# BpodFSM_r2_2.net
KiCad netlist of a schematic drawn in EAGLE
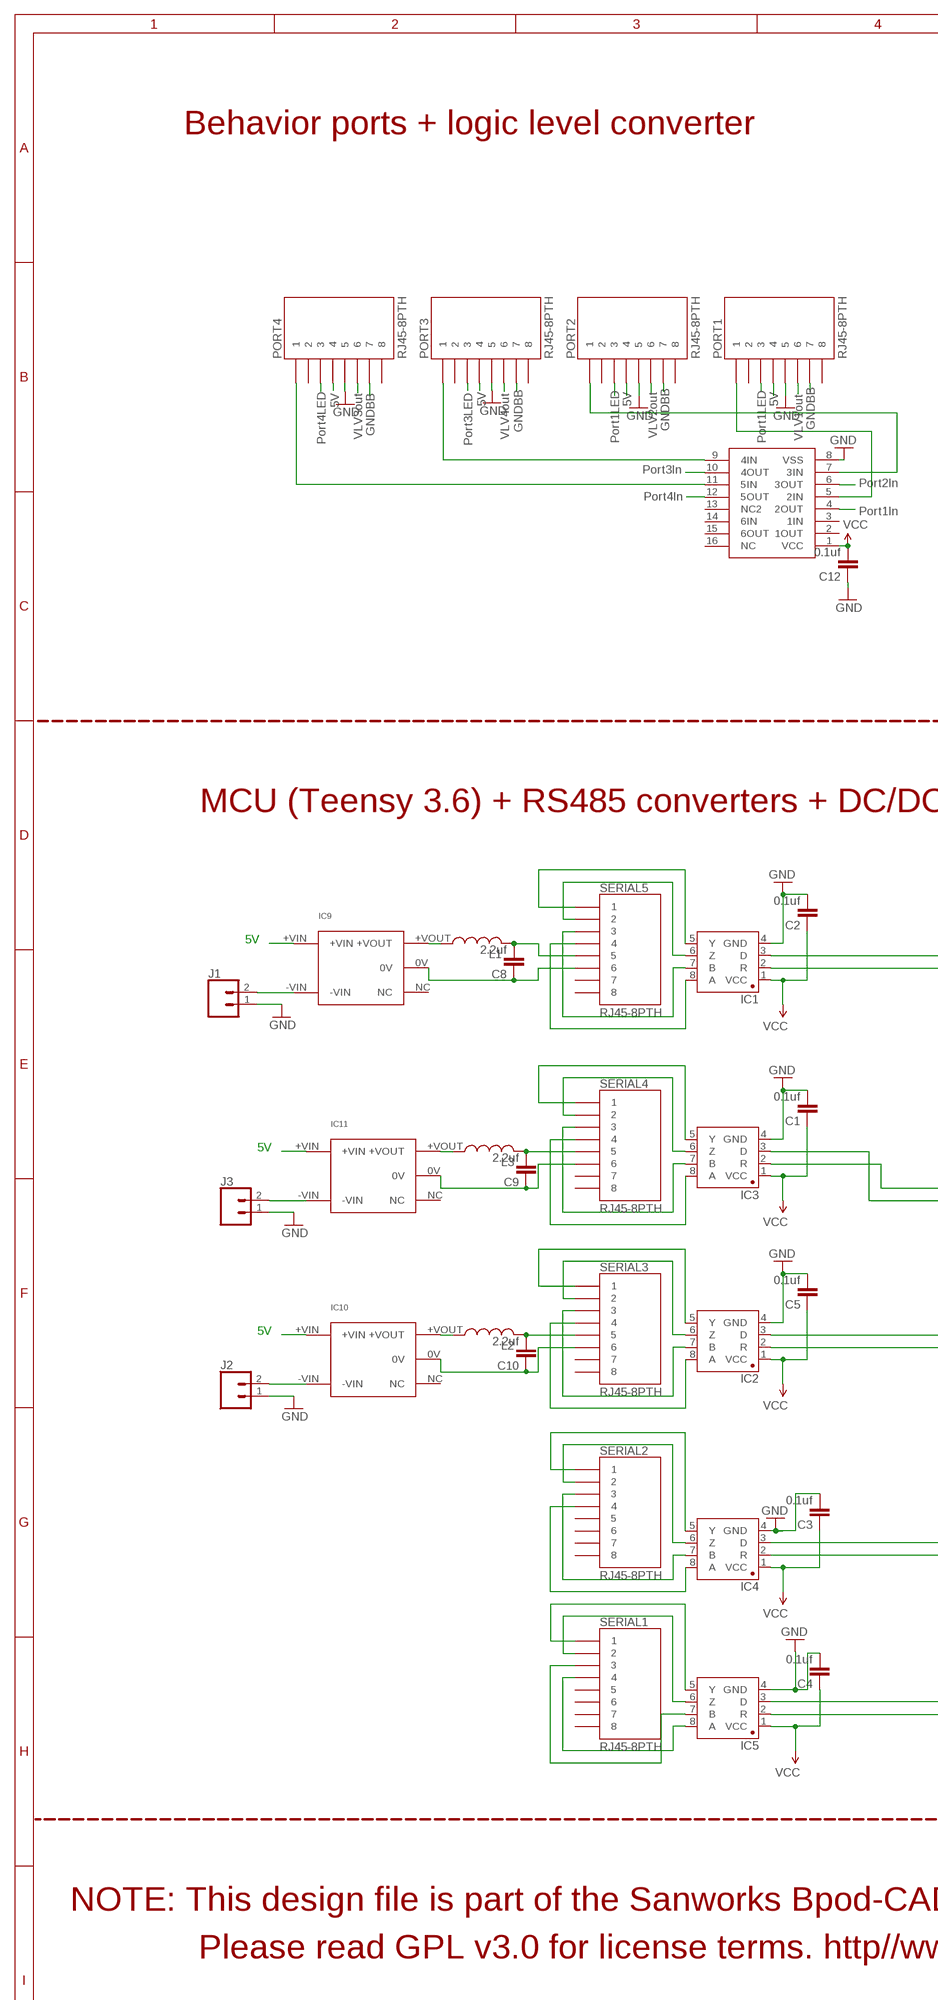
[diagram p0: schematic, sheet 1, part 1 of 2]
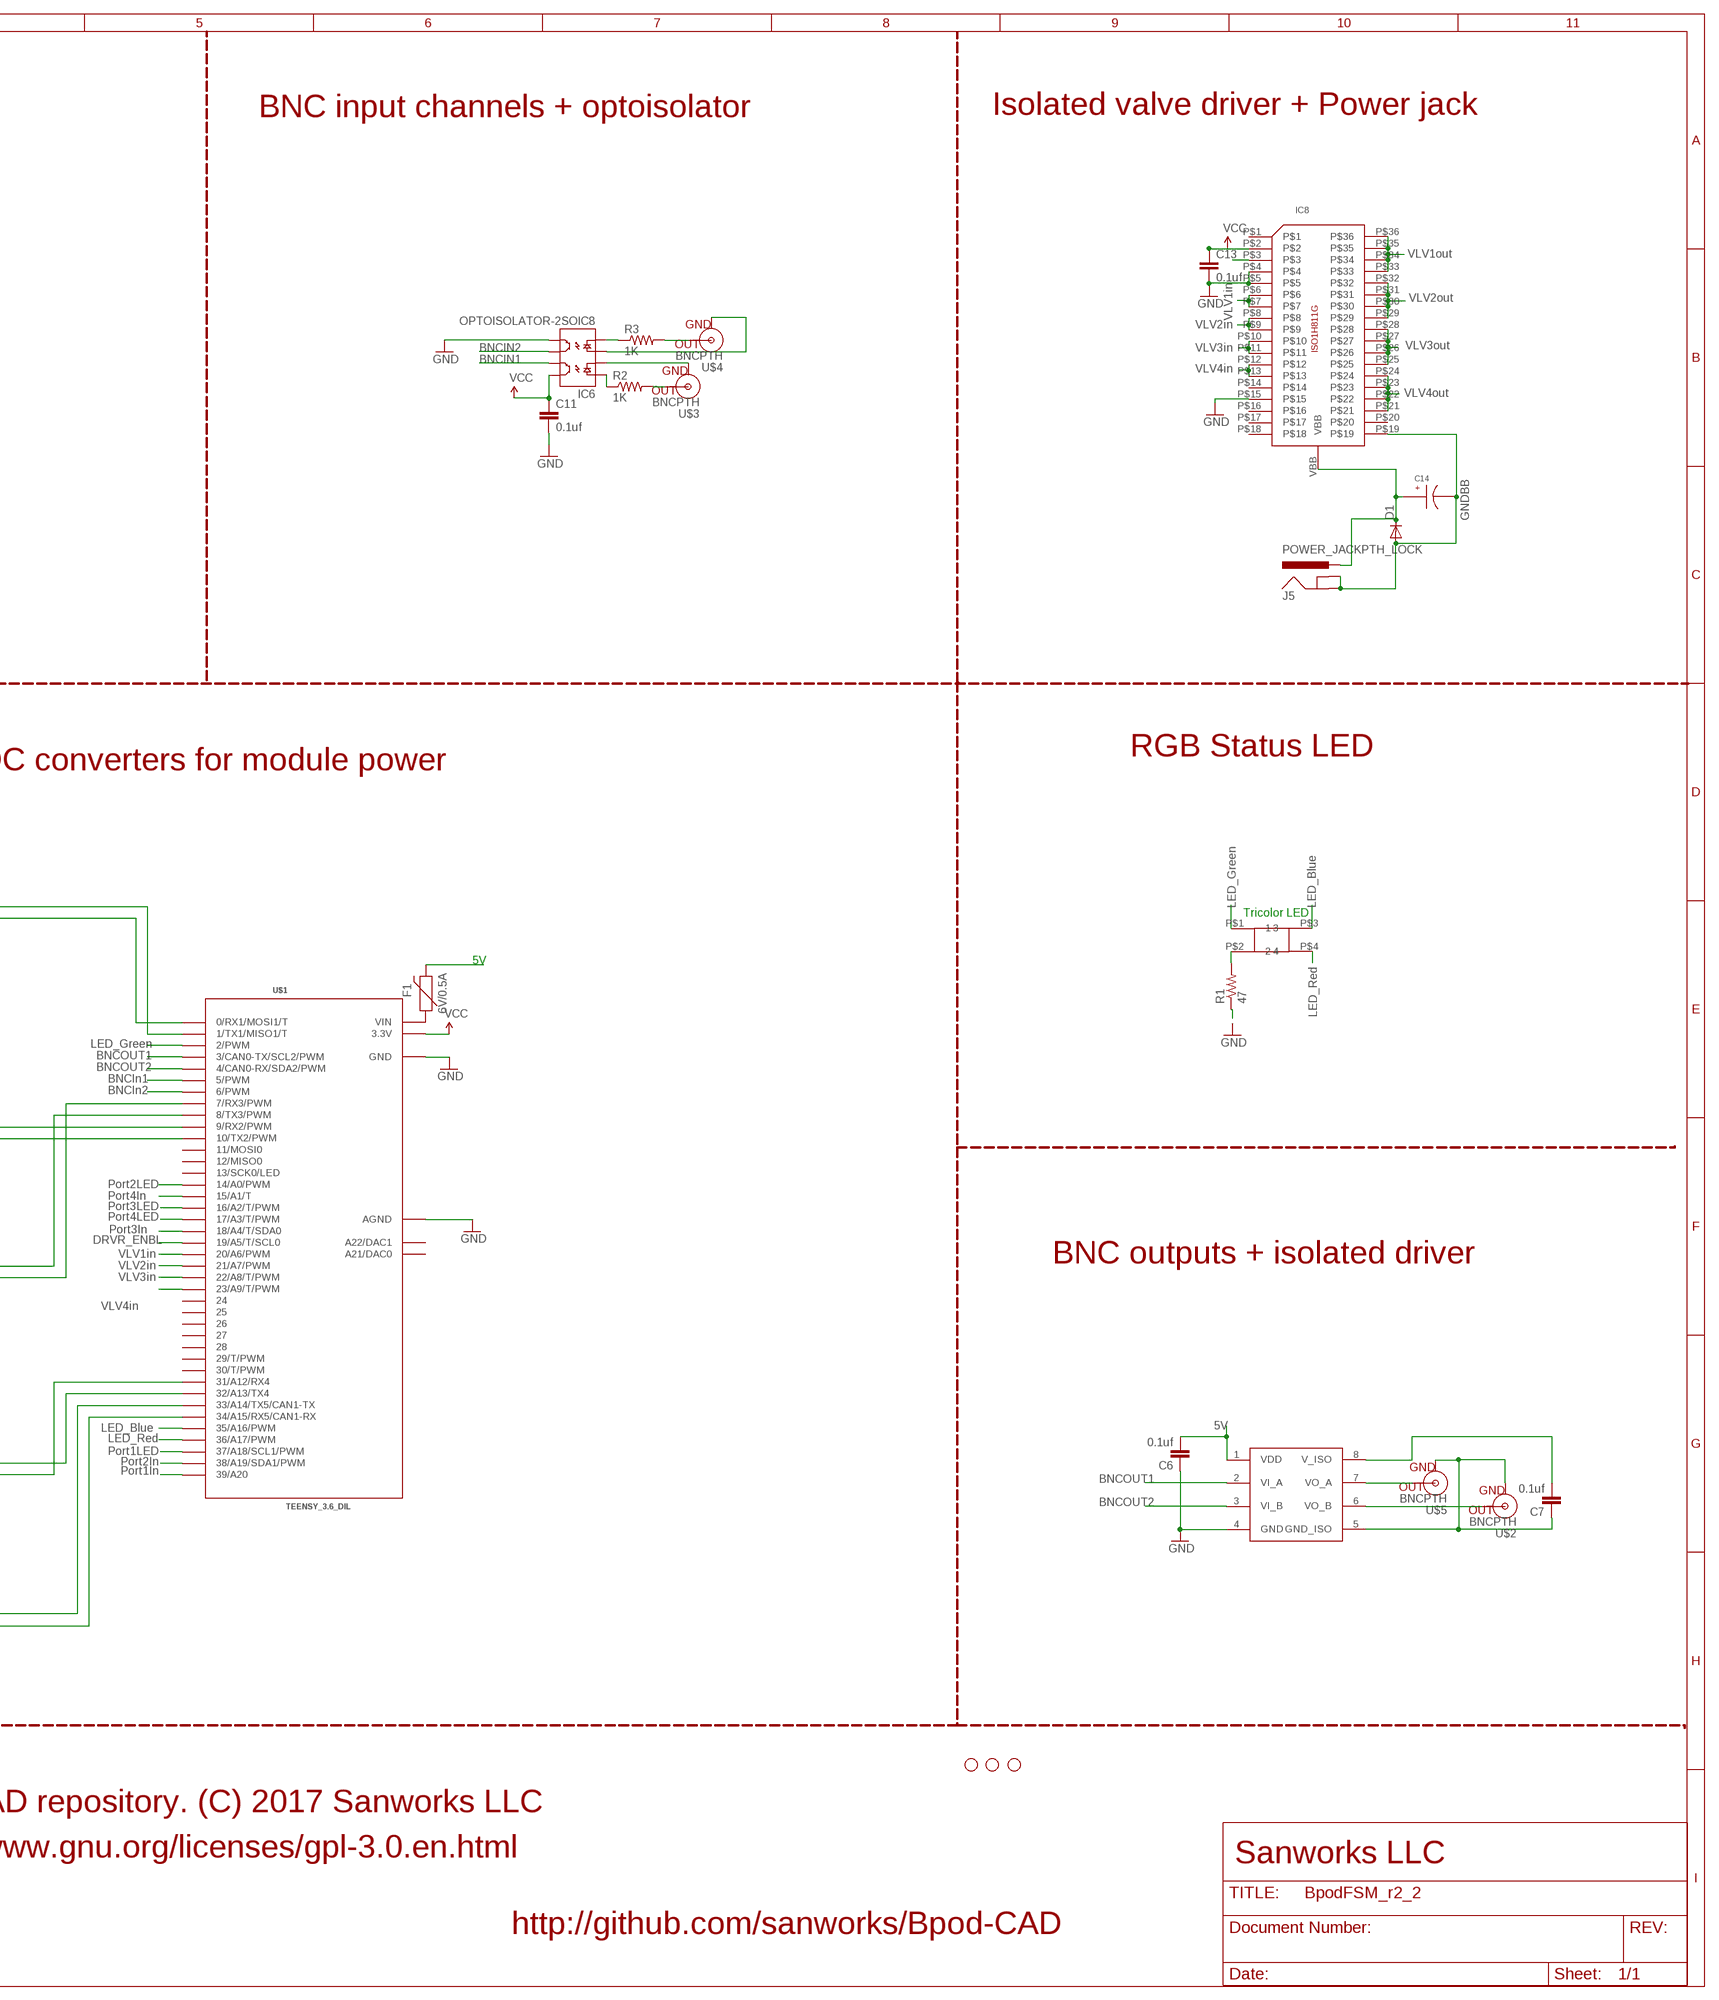
[diagram p1: schematic, sheet 1, part 2 of 2]

(export (version "E")
  (design (tool "Eeschema 10.0.6"))
  (components
    (comp (ref "C1")
      (value "0.1uf")
      (footprint "eagle-import:1206")
      (libsource (lib "eagle-import") (part "CAP1206"))
    )
    (comp (ref "C2")
      (value "0.1uf")
      (footprint "eagle-import:1206")
      (libsource (lib "eagle-import") (part "CAP1206"))
    )
    (comp (ref "C3")
      (value "0.1uf")
      (footprint "eagle-import:1206")
      (libsource (lib "eagle-import") (part "CAP1206"))
    )
    (comp (ref "C4")
      (value "0.1uf")
      (footprint "eagle-import:1206")
      (libsource (lib "eagle-import") (part "CAP1206"))
    )
    (comp (ref "C5")
      (value "0.1uf")
      (footprint "eagle-import:1206")
      (libsource (lib "eagle-import") (part "CAP1206"))
    )
    (comp (ref "C6")
      (value "0.1uf")
      (footprint "eagle-import:1206")
      (libsource (lib "eagle-import") (part "CAP1206"))
    )
    (comp (ref "C7")
      (value "0.1uf")
      (footprint "eagle-import:1206")
      (libsource (lib "eagle-import") (part "CAP1206"))
    )
    (comp (ref "C8")
      (value "2.2uf")
      (footprint "eagle-import:1206")
      (libsource (lib "eagle-import") (part "CAP1206"))
    )
    (comp (ref "C9")
      (value "2.2uf")
      (footprint "eagle-import:1206")
      (libsource (lib "eagle-import") (part "CAP1206"))
    )
    (comp (ref "C10")
      (value "2.2uf")
      (footprint "eagle-import:1206")
      (libsource (lib "eagle-import") (part "CAP1206"))
    )
    (comp (ref "C11")
      (value "0.1uf")
      (footprint "eagle-import:1206")
      (libsource (lib "eagle-import") (part "CAP1206"))
    )
    (comp (ref "C12")
      (value "0.1uf")
      (footprint "eagle-import:1206")
      (libsource (lib "eagle-import") (part "CAP1206"))
    )
    (comp (ref "C13")
      (value "0.1uf")
      (footprint "eagle-import:1206")
      (libsource (lib "eagle-import") (part "CAP1206"))
    )
    (comp (ref "C14")
      (value "EEE-FK1H100UR")
      (footprint "eagle-import:EEE-FK1H100UR")
      (libsource (lib "eagle-import") (part "EEE-FK1H100UR"))
    )
    (comp (ref "D1")
      (value "DIODE-DO214AA")
      (footprint "eagle-import:DO214AA")
      (libsource (lib "eagle-import") (part "DIODE-DO214AA"))
    )
    (comp (ref "F1")
      (value "6V/0.5A")
      (footprint "eagle-import:1206")
      (libsource (lib "eagle-import") (part "PPTC_HALF-AMP"))
    )
    (comp (ref "IC1")
      (value "SN65HVD31DR")
      (footprint "eagle-import:SO08")
      (libsource (lib "eagle-import") (part "SN65HVD31DR"))
    )
    (comp (ref "IC2")
      (value "SN65HVD31DR")
      (footprint "eagle-import:SO08")
      (libsource (lib "eagle-import") (part "SN65HVD31DR"))
    )
    (comp (ref "IC3")
      (value "SN65HVD31DR")
      (footprint "eagle-import:SO08")
      (libsource (lib "eagle-import") (part "SN65HVD31DR"))
    )
    (comp (ref "IC4")
      (value "SN65HVD31DR")
      (footprint "eagle-import:SO08")
      (libsource (lib "eagle-import") (part "SN65HVD31DR"))
    )
    (comp (ref "IC5")
      (value "SN65HVD31DR")
      (footprint "eagle-import:SO08")
      (libsource (lib "eagle-import") (part "SN65HVD31DR"))
    )
    (comp (ref "IC6")
      (value "OPTOISOLATOR-2SOIC8")
      (footprint "eagle-import:SO08-2")
      (libsource (lib "eagle-import") (part "OPTOISOLATOR-2SOIC8"))
    )
    (comp (ref "IC7")
      (value "ADUM5240")
      (footprint "eagle-import:SO08")
      (libsource (lib "eagle-import") (part "ADUM5240"))
    )
    (comp (ref "IC8")
      (value "ISO1H811G")
      (footprint "eagle-import:ISO1H811G")
      (libsource (lib "eagle-import") (part "ISO1H811G"))
    )
    (comp (ref "IC9")
      (value "MTU1D0505MC")
      (footprint "eagle-import:MTU1D0505MC")
      (libsource (lib "eagle-import") (part "MTU1D0505MC"))
    )
    (comp (ref "IC10")
      (value "MTU1D0505MC")
      (footprint "eagle-import:MTU1D0505MC")
      (libsource (lib "eagle-import") (part "MTU1D0505MC"))
    )
    (comp (ref "IC11")
      (value "MTU1D0505MC")
      (footprint "eagle-import:MTU1D0505MC")
      (libsource (lib "eagle-import") (part "MTU1D0505MC"))
    )
    (comp (ref "IC12")
      (value "CD4050")
      (footprint "eagle-import:SO16")
      (libsource (lib "eagle-import") (part "CD4050"))
    )
    (comp (ref "J1")
      (value "CONN_02")
      (footprint "eagle-import:1X02")
      (libsource (lib "eagle-import") (part "CONN_02"))
    )
    (comp (ref "J2")
      (value "CONN_02")
      (footprint "eagle-import:1X02")
      (libsource (lib "eagle-import") (part "CONN_02"))
    )
    (comp (ref "J3")
      (value "CONN_02")
      (footprint "eagle-import:1X02")
      (libsource (lib "eagle-import") (part "CONN_02"))
    )
    (comp (ref "J5")
      (value "POWER_JACKPTH_LOCK")
      (footprint "eagle-import:POWER_JACK_PTH_LOCK")
      (libsource (lib "eagle-import") (part "POWER_JACKPTH_LOCK"))
    )
    (comp (ref "JP3")
      (value "STAND-OFF")
      (footprint "eagle-import:STAND-OFF")
      (libsource (lib "eagle-import") (part "STAND-OFF"))
    )
    (comp (ref "JP4")
      (value "STAND-OFF")
      (footprint "eagle-import:STAND-OFF")
      (libsource (lib "eagle-import") (part "STAND-OFF"))
    )
    (comp (ref "JP5")
      (value "STAND-OFF")
      (footprint "eagle-import:STAND-OFF")
      (libsource (lib "eagle-import") (part "STAND-OFF"))
    )
    (comp (ref "L1")
      (value "L-USL3225M")
      (footprint "eagle-import:L3225M")
      (libsource (lib "eagle-import") (part "L-USL3225M"))
    )
    (comp (ref "L2")
      (value "L-USL3225M")
      (footprint "eagle-import:L3225M")
      (libsource (lib "eagle-import") (part "L-USL3225M"))
    )
    (comp (ref "L3")
      (value "L-USL3225M")
      (footprint "eagle-import:L3225M")
      (libsource (lib "eagle-import") (part "L-USL3225M"))
    )
    (comp (ref "PORT1")
      (value "RJ45-8PTH")
      (footprint "eagle-import:RJ45-8")
      (libsource (lib "eagle-import") (part "RJ45-8PTH"))
    )
    (comp (ref "PORT2")
      (value "RJ45-8PTH")
      (footprint "eagle-import:RJ45-8")
      (libsource (lib "eagle-import") (part "RJ45-8PTH"))
    )
    (comp (ref "PORT3")
      (value "RJ45-8PTH")
      (footprint "eagle-import:RJ45-8")
      (libsource (lib "eagle-import") (part "RJ45-8PTH"))
    )
    (comp (ref "PORT4")
      (value "RJ45-8PTH")
      (footprint "eagle-import:RJ45-8")
      (libsource (lib "eagle-import") (part "RJ45-8PTH"))
    )
    (comp (ref "R1")
      (value "47")
      (footprint "eagle-import:1206")
      (libsource (lib "eagle-import") (part "RESISTOR1206"))
    )
    (comp (ref "R2")
      (value "1K")
      (footprint "eagle-import:1206")
      (libsource (lib "eagle-import") (part "SparkFun-Resistors_RESISTOR1206"))
    )
    (comp (ref "R3")
      (value "1K")
      (footprint "eagle-import:1206")
      (libsource (lib "eagle-import") (part "SparkFun-Resistors_RESISTOR1206"))
    )
    (comp (ref "SERIAL1")
      (value "RJ45-8PTH")
      (footprint "eagle-import:RJ45-8")
      (libsource (lib "eagle-import") (part "RJ45-8PTH"))
    )
    (comp (ref "SERIAL2")
      (value "RJ45-8PTH")
      (footprint "eagle-import:RJ45-8")
      (libsource (lib "eagle-import") (part "RJ45-8PTH"))
    )
    (comp (ref "SERIAL3")
      (value "RJ45-8PTH")
      (footprint "eagle-import:RJ45-8")
      (libsource (lib "eagle-import") (part "RJ45-8PTH"))
    )
    (comp (ref "SERIAL4")
      (value "RJ45-8PTH")
      (footprint "eagle-import:RJ45-8")
      (libsource (lib "eagle-import") (part "RJ45-8PTH"))
    )
    (comp (ref "SERIAL5")
      (value "RJ45-8PTH")
      (footprint "eagle-import:RJ45-8")
      (libsource (lib "eagle-import") (part "RJ45-8PTH"))
    )
    (comp (ref "U$1")
      (value "TEENSY_3.6_DIL")
      (footprint "eagle-import:TEENSY_3.6_DIL")
      (libsource (lib "eagle-import") (part "TEENSY_3.6_DIL"))
    )
    (comp (ref "U$2")
      (value "BNCPTH")
      (footprint "eagle-import:BNC")
      (libsource (lib "eagle-import") (part "BNCPTH"))
    )
    (comp (ref "U$3")
      (value "BNCPTH")
      (footprint "eagle-import:BNC")
      (libsource (lib "eagle-import") (part "BNCPTH"))
    )
    (comp (ref "U$4")
      (value "BNCPTH")
      (footprint "eagle-import:BNC")
      (libsource (lib "eagle-import") (part "BNCPTH"))
    )
    (comp (ref "U$5")
      (value "BNCPTH")
      (footprint "eagle-import:BNC")
      (libsource (lib "eagle-import") (part "BNCPTH"))
    )
    (comp (ref "U$8")
      (value "SQUARE_TRICOLOR_LED")
      (footprint "eagle-import:SQUARE_TRICOLOR_LED")
      (libsource (lib "eagle-import") (part "SQUARE_TRICOLOR_LED"))
    )
  )
  (nets
    (net (code "1") (name "/5V") (class "Default")
      (node (ref "C6") (pin "2") (pinfunction "2_2") (pintype "passive"))
      (node (ref "F1") (pin "2") (pinfunction "2_2") (pintype "bidirectional"))
      (node (ref "IC10") (pin "+VIN") (pinfunction "+VIN_+VIN") (pintype "bidirectional"))
      (node (ref "IC11") (pin "+VIN") (pinfunction "+VIN_+VIN") (pintype "bidirectional"))
      (node (ref "IC7") (pin "1") (pinfunction "VDD_1") (pintype "bidirectional"))
      (node (ref "IC9") (pin "+VIN") (pinfunction "+VIN_+VIN") (pintype "bidirectional"))
      (node (ref "PORT1") (pin "4") (pinfunction "4_4") (pintype "bidirectional"))
      (node (ref "PORT2") (pin "4") (pinfunction "4_4") (pintype "bidirectional"))
      (node (ref "PORT3") (pin "4") (pinfunction "4_4") (pintype "bidirectional"))
      (node (ref "PORT4") (pin "4") (pinfunction "4_4") (pintype "bidirectional"))
    )
    (net (code "2") (name "/BNCIN1") (class "Default")
      (node (ref "IC6") (pin "7") (pinfunction "EM1_7") (pintype "bidirectional"))
      (node (ref "U$1") (pin "6") (pinfunction "6/PWM_6") (pintype "bidirectional"))
    )
    (net (code "3") (name "/BNCIN2") (class "Default")
      (node (ref "IC6") (pin "6") (pinfunction "CL2_6") (pintype "bidirectional"))
      (node (ref "U$1") (pin "5") (pinfunction "5/PWM_5") (pintype "bidirectional"))
    )
    (net (code "4") (name "/BNCOUT1") (class "Default")
      (node (ref "IC7") (pin "3") (pinfunction "VI_B_3") (pintype "bidirectional"))
      (node (ref "U$1") (pin "4") (pinfunction "4/CAN0-RX/SDA2/PWM_4") (pintype "bidirectional"))
    )
    (net (code "5") (name "/BNCOUT2") (class "Default")
      (node (ref "IC7") (pin "2") (pinfunction "VI_A_2") (pintype "bidirectional"))
      (node (ref "U$1") (pin "3") (pinfunction "3/CAN0-TX/SCL2/PWM_3") (pintype "bidirectional"))
    )
    (net (code "6") (name "/DRVR_ENBL") (class "Default")
      (node (ref "IC8") (pin "P$3") (pinfunction "P$3_P$3") (pintype "bidirectional"))
      (node (ref "U$1") (pin "19/A5") (pinfunction "19/A5/T/SCL0_19/A5") (pintype "bidirectional"))
    )
    (net (code "7") (name "/GNDBB") (class "Default")
      (node (ref "C14") (pin "CATHODE") (pinfunction "CATHODE_CATHODE") (pintype "bidirectional"))
      (node (ref "D1") (pin "A") (pinfunction "A_A") (pintype "passive"))
      (node (ref "IC8") (pin "P$19") (pinfunction "P$19_P$19") (pintype "bidirectional"))
      (node (ref "J5") (pin "GND") (pinfunction "GND_GND") (pintype "bidirectional"))
      (node (ref "J5") (pin "GNDBREAK") (pinfunction "GNDBREAK_GNDBREAK") (pintype "bidirectional"))
      (node (ref "PORT1") (pin "7") (pinfunction "7_7") (pintype "bidirectional"))
      (node (ref "PORT2") (pin "7") (pinfunction "7_7") (pintype "bidirectional"))
      (node (ref "PORT3") (pin "7") (pinfunction "7_7") (pintype "bidirectional"))
      (node (ref "PORT4") (pin "7") (pinfunction "7_7") (pintype "bidirectional"))
    )
    (net (code "8") (name "/LED_BLUE") (class "Default")
      (node (ref "U$1") (pin "35/A16") (pinfunction "35/A16/PWM_35/A16") (pintype "bidirectional"))
      (node (ref "U$8") (pin "P$3") (pinfunction "3_P$3") (pintype "bidirectional"))
    )
    (net (code "9") (name "/LED_GREEN") (class "Default")
      (node (ref "U$1") (pin "2") (pinfunction "2/PWM_2") (pintype "bidirectional"))
      (node (ref "U$8") (pin "P$1") (pinfunction "1_P$1") (pintype "bidirectional"))
    )
    (net (code "10") (name "/LED_RED") (class "Default")
      (node (ref "U$1") (pin "36/A17") (pinfunction "36/A17/PWM_36/A17") (pintype "bidirectional"))
      (node (ref "U$8") (pin "P$4") (pinfunction "4_P$4") (pintype "bidirectional"))
    )
    (net (code "11") (name "/PORT1IN") (class "Default")
      (node (ref "IC12") (pin "4") (pinfunction "2OUT_4") (pintype "bidirectional"))
      (node (ref "U$1") (pin "39/A20") (pinfunction "39/A20_39/A20") (pintype "bidirectional"))
    )
    (net (code "12") (name "/PORT1LED") (class "Default")
      (node (ref "PORT1") (pin "3") (pinfunction "3_3") (pintype "bidirectional"))
      (node (ref "U$1") (pin "37/A18") (pinfunction "37/A18/SCL1/PWM_37/A18") (pintype "bidirectional"))
    )
    (net (code "13") (name "/PORT2IN") (class "Default")
      (node (ref "IC12") (pin "6") (pinfunction "3OUT_6") (pintype "bidirectional"))
      (node (ref "U$1") (pin "38/A19") (pinfunction "38/A19/SDA1/PWM_38/A19") (pintype "bidirectional"))
    )
    (net (code "14") (name "/PORT2LED") (class "Default")
      (node (ref "PORT2") (pin "3") (pinfunction "3_3") (pintype "bidirectional"))
      (node (ref "U$1") (pin "14/A0") (pinfunction "14/A0/PWM_14/A0") (pintype "bidirectional"))
    )
    (net (code "15") (name "/PORT3IN") (class "Default")
      (node (ref "IC12") (pin "10") (pinfunction "4OUT_10") (pintype "bidirectional"))
      (node (ref "U$1") (pin "18/A4") (pinfunction "18/A4/T/SDA0_18/A4") (pintype "bidirectional"))
    )
    (net (code "16") (name "/PORT3LED") (class "Default")
      (node (ref "PORT3") (pin "3") (pinfunction "3_3") (pintype "bidirectional"))
      (node (ref "U$1") (pin "16/A2") (pinfunction "16/A2/T/PWM_16/A2") (pintype "bidirectional"))
    )
    (net (code "17") (name "/PORT4IN") (class "Default")
      (node (ref "IC12") (pin "12") (pinfunction "5OUT_12") (pintype "bidirectional"))
      (node (ref "U$1") (pin "15/A1") (pinfunction "15/A1/T_15/A1") (pintype "bidirectional"))
    )
    (net (code "18") (name "/PORT4LED") (class "Default")
      (node (ref "PORT4") (pin "3") (pinfunction "3_3") (pintype "bidirectional"))
      (node (ref "U$1") (pin "17/A3") (pinfunction "17/A3/T/PWM_17/A3") (pintype "bidirectional"))
    )
    (net (code "19") (name "/VLV1IN") (class "Default")
      (node (ref "IC8") (pin "P$6") (pinfunction "P$6_P$6") (pintype "bidirectional"))
      (node (ref "IC8") (pin "P$7") (pinfunction "P$7_P$7") (pintype "bidirectional"))
      (node (ref "U$1") (pin "23/A9") (pinfunction "23/A9/T/PWM_23/A9") (pintype "bidirectional"))
    )
    (net (code "20") (name "/VLV1OUT") (class "Default")
      (node (ref "IC8") (pin "P$33") (pinfunction "P$33_P$33") (pintype "bidirectional"))
      (node (ref "IC8") (pin "P$34") (pinfunction "P$34_P$34") (pintype "bidirectional"))
      (node (ref "IC8") (pin "P$35") (pinfunction "P$35_P$35") (pintype "bidirectional"))
      (node (ref "IC8") (pin "P$36") (pinfunction "P$36_P$36") (pintype "bidirectional"))
      (node (ref "PORT1") (pin "6") (pinfunction "6_6") (pintype "bidirectional"))
    )
    (net (code "21") (name "/VLV2IN") (class "Default")
      (node (ref "IC8") (pin "P$8") (pinfunction "P$8_P$8") (pintype "bidirectional"))
      (node (ref "IC8") (pin "P$9") (pinfunction "P$9_P$9") (pintype "bidirectional"))
      (node (ref "U$1") (pin "22/A8") (pinfunction "22/A8/T/PWM_22/A8") (pintype "bidirectional"))
    )
    (net (code "22") (name "/VLV2OUT") (class "Default")
      (node (ref "IC8") (pin "P$29") (pinfunction "P$29_P$29") (pintype "bidirectional"))
      (node (ref "IC8") (pin "P$30") (pinfunction "P$30_P$30") (pintype "bidirectional"))
      (node (ref "IC8") (pin "P$31") (pinfunction "P$31_P$31") (pintype "bidirectional"))
      (node (ref "IC8") (pin "P$32") (pinfunction "P$32_P$32") (pintype "bidirectional"))
      (node (ref "PORT2") (pin "6") (pinfunction "6_6") (pintype "bidirectional"))
    )
    (net (code "23") (name "/VLV3IN") (class "Default")
      (node (ref "IC8") (pin "P$12") (pinfunction "P$12_P$12") (pintype "bidirectional"))
      (node (ref "IC8") (pin "P$13") (pinfunction "P$13_P$13") (pintype "bidirectional"))
      (node (ref "U$1") (pin "20/A6") (pinfunction "20/A6/PWM_20/A6") (pintype "bidirectional"))
    )
    (net (code "24") (name "/VLV3OUT") (class "Default")
      (node (ref "IC8") (pin "P$21") (pinfunction "P$21_P$21") (pintype "bidirectional"))
      (node (ref "IC8") (pin "P$22") (pinfunction "P$22_P$22") (pintype "bidirectional"))
      (node (ref "IC8") (pin "P$23") (pinfunction "P$23_P$23") (pintype "bidirectional"))
      (node (ref "IC8") (pin "P$24") (pinfunction "P$24_P$24") (pintype "bidirectional"))
      (node (ref "PORT3") (pin "6") (pinfunction "6_6") (pintype "bidirectional"))
    )
    (net (code "25") (name "/VLV4IN") (class "Default")
      (node (ref "IC8") (pin "P$10") (pinfunction "P$10_P$10") (pintype "bidirectional"))
      (node (ref "IC8") (pin "P$11") (pinfunction "P$11_P$11") (pintype "bidirectional"))
      (node (ref "U$1") (pin "21/A7") (pinfunction "21/A7/PWM_21/A7") (pintype "bidirectional"))
    )
    (net (code "26") (name "/VLV4OUT") (class "Default")
      (node (ref "IC8") (pin "P$25") (pinfunction "P$25_P$25") (pintype "bidirectional"))
      (node (ref "IC8") (pin "P$26") (pinfunction "P$26_P$26") (pintype "bidirectional"))
      (node (ref "IC8") (pin "P$27") (pinfunction "P$27_P$27") (pintype "bidirectional"))
      (node (ref "IC8") (pin "P$28") (pinfunction "P$28_P$28") (pintype "bidirectional"))
      (node (ref "PORT4") (pin "6") (pinfunction "6_6") (pintype "bidirectional"))
    )
    (net (code "27") (name "GND") (class "Default")
      (node (ref "C1") (pin "2") (pinfunction "2_2") (pintype "passive"))
      (node (ref "C11") (pin "2") (pinfunction "2_2") (pintype "passive"))
      (node (ref "C12") (pin "1") (pinfunction "1_1") (pintype "passive"))
      (node (ref "C13") (pin "2") (pinfunction "2_2") (pintype "passive"))
      (node (ref "C2") (pin "2") (pinfunction "2_2") (pintype "passive"))
      (node (ref "C3") (pin "2") (pinfunction "2_2") (pintype "passive"))
      (node (ref "C4") (pin "2") (pinfunction "2_2") (pintype "passive"))
      (node (ref "C5") (pin "2") (pinfunction "2_2") (pintype "passive"))
      (node (ref "C6") (pin "1") (pinfunction "1_1") (pintype "passive"))
      (node (ref "IC1") (pin "4") (pinfunction "GND_4") (pintype "bidirectional"))
      (node (ref "IC12") (pin "8") (pinfunction "VSS_8") (pintype "bidirectional"))
      (node (ref "IC2") (pin "4") (pinfunction "GND_4") (pintype "bidirectional"))
      (node (ref "IC3") (pin "4") (pinfunction "GND_4") (pintype "bidirectional"))
      (node (ref "IC4") (pin "4") (pinfunction "GND_4") (pintype "bidirectional"))
      (node (ref "IC5") (pin "4") (pinfunction "GND_4") (pintype "bidirectional"))
      (node (ref "IC6") (pin "5") (pinfunction "EM2_5") (pintype "bidirectional"))
      (node (ref "IC7") (pin "4") (pinfunction "GND_4") (pintype "bidirectional"))
      (node (ref "IC8") (pin "P$15") (pinfunction "P$15_P$15") (pintype "bidirectional"))
      (node (ref "IC8") (pin "P$4") (pinfunction "P$4_P$4") (pintype "bidirectional"))
      (node (ref "IC8") (pin "P$5") (pinfunction "P$5_P$5") (pintype "bidirectional"))
      (node (ref "J1") (pin "1") (pinfunction "1_1") (pintype "passive"))
      (node (ref "J2") (pin "1") (pinfunction "1_1") (pintype "passive"))
      (node (ref "J3") (pin "1") (pinfunction "1_1") (pintype "passive"))
      (node (ref "PORT1") (pin "5") (pinfunction "5_5") (pintype "bidirectional"))
      (node (ref "PORT2") (pin "5") (pinfunction "5_5") (pintype "bidirectional"))
      (node (ref "PORT3") (pin "5") (pinfunction "5_5") (pintype "bidirectional"))
      (node (ref "PORT4") (pin "5") (pinfunction "5_5") (pintype "bidirectional"))
      (node (ref "R1") (pin "1") (pinfunction "1_1") (pintype "passive"))
      (node (ref "U$1") (pin "AGND") (pinfunction "AGND_AGND") (pintype "power_in"))
      (node (ref "U$1") (pin "GND") (pinfunction "GND_GND") (pintype "power_in"))
      (node (ref "U$1") (pin "GND1") (pinfunction "GND_GND1") (pintype "power_in"))
    )
    (net (code "28") (name "Net-(C8-Pad1)") (class "Default")
      (node (ref "C8") (pin "1") (pinfunction "1_1") (pintype "passive"))
      (node (ref "IC9") (pin "0V") (pinfunction "0V_0V") (pintype "bidirectional"))
      (node (ref "SERIAL5") (pin "6") (pinfunction "6_6") (pintype "bidirectional"))
    )
    (net (code "29") (name "Net-(C8-Pad2)") (class "Default")
      (node (ref "C8") (pin "2") (pinfunction "2_2") (pintype "passive"))
      (node (ref "L1") (pin "2") (pinfunction "2_2") (pintype "passive"))
      (node (ref "SERIAL5") (pin "5") (pinfunction "5_5") (pintype "bidirectional"))
    )
    (net (code "30") (name "Net-(C9-Pad1)") (class "Default")
      (node (ref "C9") (pin "1") (pinfunction "1_1") (pintype "passive"))
      (node (ref "IC11") (pin "0V") (pinfunction "0V_0V") (pintype "bidirectional"))
      (node (ref "SERIAL4") (pin "6") (pinfunction "6_6") (pintype "bidirectional"))
    )
    (net (code "31") (name "Net-(C9-Pad2)") (class "Default")
      (node (ref "C9") (pin "2") (pinfunction "2_2") (pintype "passive"))
      (node (ref "L3") (pin "2") (pinfunction "2_2") (pintype "passive"))
      (node (ref "SERIAL4") (pin "5") (pinfunction "5_5") (pintype "bidirectional"))
    )
    (net (code "32") (name "Net-(C10-Pad1)") (class "Default")
      (node (ref "C10") (pin "1") (pinfunction "1_1") (pintype "passive"))
      (node (ref "IC10") (pin "0V") (pinfunction "0V_0V") (pintype "bidirectional"))
      (node (ref "SERIAL3") (pin "6") (pinfunction "6_6") (pintype "bidirectional"))
    )
    (net (code "33") (name "Net-(C10-Pad2)") (class "Default")
      (node (ref "C10") (pin "2") (pinfunction "2_2") (pintype "passive"))
      (node (ref "L2") (pin "2") (pinfunction "2_2") (pintype "passive"))
      (node (ref "SERIAL3") (pin "5") (pinfunction "5_5") (pintype "bidirectional"))
    )
    (net (code "34") (name "Net-(C14-PadANODE)") (class "Default")
      (node (ref "C14") (pin "ANODE") (pinfunction "ANODE_ANODE") (pintype "bidirectional"))
      (node (ref "D1") (pin "C") (pinfunction "C_C") (pintype "passive"))
      (node (ref "IC8") (pin "VBB") (pinfunction "VBB_VBB") (pintype "bidirectional"))
      (node (ref "J5") (pin "PWR") (pinfunction "PWR_PWR") (pintype "bidirectional"))
    )
    (net (code "35") (name "Net-(F1-Pad1)") (class "Default")
      (node (ref "F1") (pin "1") (pinfunction "1_1") (pintype "bidirectional"))
      (node (ref "U$1") (pin "VIN") (pinfunction "VIN_VIN") (pintype "power_in"))
    )
    (net (code "36") (name "Net-(IC1-A)") (class "Default")
      (node (ref "IC1") (pin "8") (pinfunction "A_8") (pintype "bidirectional"))
      (node (ref "SERIAL5") (pin "4") (pinfunction "4_4") (pintype "bidirectional"))
    )
    (net (code "37") (name "Net-(IC1-B)") (class "Default")
      (node (ref "IC1") (pin "7") (pinfunction "B_7") (pintype "bidirectional"))
      (node (ref "SERIAL5") (pin "3") (pinfunction "3_3") (pintype "bidirectional"))
    )
    (net (code "38") (name "Net-(IC1-D)") (class "Default")
      (node (ref "IC1") (pin "3") (pinfunction "D_3") (pintype "bidirectional"))
      (node (ref "U$1") (pin "1") (pinfunction "1/TX1/MISO1/T_1") (pintype "bidirectional"))
    )
    (net (code "39") (name "Net-(IC1-R)") (class "Default")
      (node (ref "IC1") (pin "2") (pinfunction "R_2") (pintype "bidirectional"))
      (node (ref "U$1") (pin "0") (pinfunction "0/RX1/MOSI1/T_0") (pintype "bidirectional"))
    )
    (net (code "40") (name "Net-(IC1-Y)") (class "Default")
      (node (ref "IC1") (pin "5") (pinfunction "Y_5") (pintype "bidirectional"))
      (node (ref "SERIAL5") (pin "1") (pinfunction "1_1") (pintype "bidirectional"))
    )
    (net (code "41") (name "Net-(IC1-Z)") (class "Default")
      (node (ref "IC1") (pin "6") (pinfunction "Z_6") (pintype "bidirectional"))
      (node (ref "SERIAL5") (pin "2") (pinfunction "2_2") (pintype "bidirectional"))
    )
    (net (code "42") (name "Net-(IC2-A)") (class "Default")
      (node (ref "IC2") (pin "8") (pinfunction "A_8") (pintype "bidirectional"))
      (node (ref "SERIAL3") (pin "4") (pinfunction "4_4") (pintype "bidirectional"))
    )
    (net (code "43") (name "Net-(IC2-B)") (class "Default")
      (node (ref "IC2") (pin "7") (pinfunction "B_7") (pintype "bidirectional"))
      (node (ref "SERIAL3") (pin "3") (pinfunction "3_3") (pintype "bidirectional"))
    )
    (net (code "44") (name "Net-(IC2-D)") (class "Default")
      (node (ref "IC2") (pin "3") (pinfunction "D_3") (pintype "bidirectional"))
      (node (ref "U$1") (pin "8") (pinfunction "8/TX3/PWM_8") (pintype "bidirectional"))
    )
    (net (code "45") (name "Net-(IC2-R)") (class "Default")
      (node (ref "IC2") (pin "2") (pinfunction "R_2") (pintype "bidirectional"))
      (node (ref "U$1") (pin "7") (pinfunction "7/RX3/PWM_7") (pintype "bidirectional"))
    )
    (net (code "46") (name "Net-(IC2-Y)") (class "Default")
      (node (ref "IC2") (pin "5") (pinfunction "Y_5") (pintype "bidirectional"))
      (node (ref "SERIAL3") (pin "1") (pinfunction "1_1") (pintype "bidirectional"))
    )
    (net (code "47") (name "Net-(IC2-Z)") (class "Default")
      (node (ref "IC2") (pin "6") (pinfunction "Z_6") (pintype "bidirectional"))
      (node (ref "SERIAL3") (pin "2") (pinfunction "2_2") (pintype "bidirectional"))
    )
    (net (code "48") (name "Net-(IC3-A)") (class "Default")
      (node (ref "IC3") (pin "8") (pinfunction "A_8") (pintype "bidirectional"))
      (node (ref "SERIAL4") (pin "4") (pinfunction "4_4") (pintype "bidirectional"))
    )
    (net (code "49") (name "Net-(IC3-B)") (class "Default")
      (node (ref "IC3") (pin "7") (pinfunction "B_7") (pintype "bidirectional"))
      (node (ref "SERIAL4") (pin "3") (pinfunction "3_3") (pintype "bidirectional"))
    )
    (net (code "50") (name "Net-(IC3-D)") (class "Default")
      (node (ref "IC3") (pin "3") (pinfunction "D_3") (pintype "bidirectional"))
      (node (ref "U$1") (pin "10") (pinfunction "10/TX2/PWM_10") (pintype "bidirectional"))
    )
    (net (code "51") (name "Net-(IC3-R)") (class "Default")
      (node (ref "IC3") (pin "2") (pinfunction "R_2") (pintype "bidirectional"))
      (node (ref "U$1") (pin "9") (pinfunction "9/RX2/PWM_9") (pintype "bidirectional"))
    )
    (net (code "52") (name "Net-(IC3-Y)") (class "Default")
      (node (ref "IC3") (pin "5") (pinfunction "Y_5") (pintype "bidirectional"))
      (node (ref "SERIAL4") (pin "1") (pinfunction "1_1") (pintype "bidirectional"))
    )
    (net (code "53") (name "Net-(IC3-Z)") (class "Default")
      (node (ref "IC3") (pin "6") (pinfunction "Z_6") (pintype "bidirectional"))
      (node (ref "SERIAL4") (pin "2") (pinfunction "2_2") (pintype "bidirectional"))
    )
    (net (code "54") (name "Net-(IC4-A)") (class "Default")
      (node (ref "IC4") (pin "8") (pinfunction "A_8") (pintype "bidirectional"))
      (node (ref "SERIAL2") (pin "4") (pinfunction "4_4") (pintype "bidirectional"))
    )
    (net (code "55") (name "Net-(IC4-B)") (class "Default")
      (node (ref "IC4") (pin "7") (pinfunction "B_7") (pintype "bidirectional"))
      (node (ref "SERIAL2") (pin "3") (pinfunction "3_3") (pintype "bidirectional"))
    )
    (net (code "56") (name "Net-(IC4-D)") (class "Default")
      (node (ref "IC4") (pin "3") (pinfunction "D_3") (pintype "bidirectional"))
      (node (ref "U$1") (pin "32/A13") (pinfunction "32/A13/TX4_32/A13") (pintype "bidirectional"))
    )
    (net (code "57") (name "Net-(IC4-R)") (class "Default")
      (node (ref "IC4") (pin "2") (pinfunction "R_2") (pintype "bidirectional"))
      (node (ref "U$1") (pin "31/A12") (pinfunction "31/A12/RX4_31/A12") (pintype "bidirectional"))
    )
    (net (code "58") (name "Net-(IC4-Y)") (class "Default")
      (node (ref "IC4") (pin "5") (pinfunction "Y_5") (pintype "bidirectional"))
      (node (ref "SERIAL2") (pin "1") (pinfunction "1_1") (pintype "bidirectional"))
    )
    (net (code "59") (name "Net-(IC4-Z)") (class "Default")
      (node (ref "IC4") (pin "6") (pinfunction "Z_6") (pintype "bidirectional"))
      (node (ref "SERIAL2") (pin "2") (pinfunction "2_2") (pintype "bidirectional"))
    )
    (net (code "60") (name "Net-(IC5-A)") (class "Default")
      (node (ref "IC5") (pin "8") (pinfunction "A_8") (pintype "bidirectional"))
      (node (ref "SERIAL1") (pin "4") (pinfunction "4_4") (pintype "bidirectional"))
    )
    (net (code "61") (name "Net-(IC5-B)") (class "Default")
      (node (ref "IC5") (pin "7") (pinfunction "B_7") (pintype "bidirectional"))
      (node (ref "SERIAL1") (pin "3") (pinfunction "3_3") (pintype "bidirectional"))
    )
    (net (code "62") (name "Net-(IC5-D)") (class "Default")
      (node (ref "IC5") (pin "3") (pinfunction "D_3") (pintype "bidirectional"))
      (node (ref "U$1") (pin "33/A14") (pinfunction "33/A14/TX5/CAN1-TX_33/A14") (pintype "bidirectional"))
    )
    (net (code "63") (name "Net-(IC5-R)") (class "Default")
      (node (ref "IC5") (pin "2") (pinfunction "R_2") (pintype "bidirectional"))
      (node (ref "U$1") (pin "34/A15") (pinfunction "34/A15/RX5/CAN1-RX_34/A15") (pintype "bidirectional"))
    )
    (net (code "64") (name "Net-(IC5-Y)") (class "Default")
      (node (ref "IC5") (pin "5") (pinfunction "Y_5") (pintype "bidirectional"))
      (node (ref "SERIAL1") (pin "1") (pinfunction "1_1") (pintype "bidirectional"))
    )
    (net (code "65") (name "Net-(IC5-Z)") (class "Default")
      (node (ref "IC5") (pin "6") (pinfunction "Z_6") (pintype "bidirectional"))
      (node (ref "SERIAL1") (pin "2") (pinfunction "2_2") (pintype "bidirectional"))
    )
    (net (code "66") (name "Net-(IC6-A1)") (class "Default")
      (node (ref "IC6") (pin "1") (pinfunction "A1_1") (pintype "bidirectional"))
      (node (ref "R2") (pin "1") (pinfunction "1_1") (pintype "passive"))
    )
    (net (code "67") (name "Net-(IC6-A2)") (class "Default")
      (node (ref "IC6") (pin "3") (pinfunction "A2_3") (pintype "bidirectional"))
      (node (ref "U$4") (pin "GND") (pinfunction "GND_GND") (pintype "bidirectional"))
    )
    (net (code "68") (name "Net-(IC6-C1)") (class "Default")
      (node (ref "IC6") (pin "2") (pinfunction "C1_2") (pintype "bidirectional"))
      (node (ref "U$3") (pin "GND") (pinfunction "GND_GND") (pintype "bidirectional"))
    )
    (net (code "69") (name "Net-(IC6-C2)") (class "Default")
      (node (ref "IC6") (pin "4") (pinfunction "C2_4") (pintype "bidirectional"))
      (node (ref "R3") (pin "1") (pinfunction "1_1") (pintype "passive"))
    )
    (net (code "70") (name "Net-(IC7-GND_ISO)") (class "Default")
      (node (ref "C7") (pin "1") (pinfunction "1_1") (pintype "passive"))
      (node (ref "IC7") (pin "5") (pinfunction "GND_ISO_5") (pintype "bidirectional"))
      (node (ref "U$2") (pin "GND") (pinfunction "GND_GND") (pintype "bidirectional"))
      (node (ref "U$5") (pin "GND") (pinfunction "GND_GND") (pintype "bidirectional"))
    )
    (net (code "71") (name "Net-(IC7-VO_A)") (class "Default")
      (node (ref "IC7") (pin "7") (pinfunction "VO_A_7") (pintype "bidirectional"))
      (node (ref "U$5") (pin "S") (pinfunction "OUT_S") (pintype "bidirectional"))
    )
    (net (code "72") (name "Net-(IC7-VO_B)") (class "Default")
      (node (ref "IC7") (pin "6") (pinfunction "VO_B_6") (pintype "bidirectional"))
      (node (ref "U$2") (pin "S") (pinfunction "OUT_S") (pintype "bidirectional"))
    )
    (net (code "73") (name "Net-(IC7-V_ISO)") (class "Default")
      (node (ref "C7") (pin "2") (pinfunction "2_2") (pintype "passive"))
      (node (ref "IC7") (pin "8") (pinfunction "V_ISO_8") (pintype "bidirectional"))
    )
    (net (code "74") (name "Net-(IC9-Pad+VOUT)") (class "Default")
      (node (ref "IC9") (pin "+VOUT") (pinfunction "+VOUT_+VOUT") (pintype "bidirectional"))
      (node (ref "L1") (pin "1") (pinfunction "1_1") (pintype "passive"))
    )
    (net (code "75") (name "Net-(IC9-Pad-VIN)") (class "Default")
      (node (ref "IC9") (pin "-VIN") (pinfunction "-VIN_-VIN") (pintype "bidirectional"))
      (node (ref "J1") (pin "2") (pinfunction "2_2") (pintype "passive"))
    )
    (net (code "76") (name "Net-(IC10-Pad+VOUT)") (class "Default")
      (node (ref "IC10") (pin "+VOUT") (pinfunction "+VOUT_+VOUT") (pintype "bidirectional"))
      (node (ref "L2") (pin "1") (pinfunction "1_1") (pintype "passive"))
    )
    (net (code "77") (name "Net-(IC10-Pad-VIN)") (class "Default")
      (node (ref "IC10") (pin "-VIN") (pinfunction "-VIN_-VIN") (pintype "bidirectional"))
      (node (ref "J2") (pin "2") (pinfunction "2_2") (pintype "passive"))
    )
    (net (code "78") (name "Net-(IC11-Pad+VOUT)") (class "Default")
      (node (ref "IC11") (pin "+VOUT") (pinfunction "+VOUT_+VOUT") (pintype "bidirectional"))
      (node (ref "L3") (pin "1") (pinfunction "1_1") (pintype "passive"))
    )
    (net (code "79") (name "Net-(IC11-Pad-VIN)") (class "Default")
      (node (ref "IC11") (pin "-VIN") (pinfunction "-VIN_-VIN") (pintype "bidirectional"))
      (node (ref "J3") (pin "2") (pinfunction "2_2") (pintype "passive"))
    )
    (net (code "80") (name "Net-(IC12-2IN)") (class "Default")
      (node (ref "IC12") (pin "5") (pinfunction "2IN_5") (pintype "bidirectional"))
      (node (ref "PORT1") (pin "1") (pinfunction "1_1") (pintype "bidirectional"))
    )
    (net (code "81") (name "Net-(IC12-3IN)") (class "Default")
      (node (ref "IC12") (pin "7") (pinfunction "3IN_7") (pintype "bidirectional"))
      (node (ref "PORT2") (pin "1") (pinfunction "1_1") (pintype "bidirectional"))
    )
    (net (code "82") (name "Net-(IC12-4IN)") (class "Default")
      (node (ref "IC12") (pin "9") (pinfunction "4IN_9") (pintype "bidirectional"))
      (node (ref "PORT3") (pin "1") (pinfunction "1_1") (pintype "bidirectional"))
    )
    (net (code "83") (name "Net-(IC12-5IN)") (class "Default")
      (node (ref "IC12") (pin "11") (pinfunction "5IN_11") (pintype "bidirectional"))
      (node (ref "PORT4") (pin "1") (pinfunction "1_1") (pintype "bidirectional"))
    )
    (net (code "84") (name "Net-(U$3-OUT)") (class "Default")
      (node (ref "R2") (pin "2") (pinfunction "2_2") (pintype "passive"))
      (node (ref "U$3") (pin "S") (pinfunction "OUT_S") (pintype "bidirectional"))
    )
    (net (code "85") (name "Net-(U$4-OUT)") (class "Default")
      (node (ref "R3") (pin "2") (pinfunction "2_2") (pintype "passive"))
      (node (ref "U$4") (pin "S") (pinfunction "OUT_S") (pintype "bidirectional"))
    )
    (net (code "86") (name "Net-(U$8-2)") (class "Default")
      (node (ref "R1") (pin "2") (pinfunction "2_2") (pintype "passive"))
      (node (ref "U$8") (pin "P$2") (pinfunction "2_P$2") (pintype "bidirectional"))
    )
    (net (code "87") (name "VCC") (class "Default")
      (node (ref "C1") (pin "1") (pinfunction "1_1") (pintype "passive"))
      (node (ref "C11") (pin "1") (pinfunction "1_1") (pintype "passive"))
      (node (ref "C12") (pin "2") (pinfunction "2_2") (pintype "passive"))
      (node (ref "C13") (pin "1") (pinfunction "1_1") (pintype "passive"))
      (node (ref "C2") (pin "1") (pinfunction "1_1") (pintype "passive"))
      (node (ref "C3") (pin "1") (pinfunction "1_1") (pintype "passive"))
      (node (ref "C4") (pin "1") (pinfunction "1_1") (pintype "passive"))
      (node (ref "C5") (pin "1") (pinfunction "1_1") (pintype "passive"))
      (node (ref "IC1") (pin "1") (pinfunction "VCC_1") (pintype "bidirectional"))
      (node (ref "IC12") (pin "1") (pinfunction "VCC_1") (pintype "bidirectional"))
      (node (ref "IC2") (pin "1") (pinfunction "VCC_1") (pintype "bidirectional"))
      (node (ref "IC3") (pin "1") (pinfunction "VCC_1") (pintype "bidirectional"))
      (node (ref "IC4") (pin "1") (pinfunction "VCC_1") (pintype "bidirectional"))
      (node (ref "IC5") (pin "1") (pinfunction "VCC_1") (pintype "bidirectional"))
      (node (ref "IC6") (pin "8") (pinfunction "CL1_8") (pintype "bidirectional"))
      (node (ref "IC8") (pin "P$2") (pinfunction "P$2_P$2") (pintype "bidirectional"))
      (node (ref "U$1") (pin "3.3V") (pinfunction "3.3V_3.3V") (pintype "power_in"))
      (node (ref "U$1") (pin "3.3V3") (pinfunction "3.3V_3.3V3") (pintype "power_in"))
    )
    (net (code "88") (name "unconnected-(IC8-PadP$1)") (class "Default")
      (node (ref "IC8") (pin "P$1") (pinfunction "P$1_P$1") (pintype "bidirectional"))
    )
    (net (code "89") (name "unconnected-(IC8-PadP$14)") (class "Default")
      (node (ref "IC8") (pin "P$14") (pinfunction "P$14_P$14") (pintype "bidirectional"))
    )
    (net (code "90") (name "unconnected-(IC8-PadP$16)") (class "Default")
      (node (ref "IC8") (pin "P$16") (pinfunction "P$16_P$16") (pintype "bidirectional"))
    )
    (net (code "91") (name "unconnected-(IC8-PadP$17)") (class "Default")
      (node (ref "IC8") (pin "P$17") (pinfunction "P$17_P$17") (pintype "bidirectional"))
    )
    (net (code "92") (name "unconnected-(IC8-PadP$18)") (class "Default")
      (node (ref "IC8") (pin "P$18") (pinfunction "P$18_P$18") (pintype "bidirectional"))
    )
    (net (code "93") (name "unconnected-(IC8-PadP$20)") (class "Default")
      (node (ref "IC8") (pin "P$20") (pinfunction "P$20_P$20") (pintype "bidirectional"))
    )
    (net (code "94") (name "unconnected-(IC9-PadNC)") (class "Default")
      (node (ref "IC9") (pin "NC") (pinfunction "NC_NC") (pintype "bidirectional"))
    )
    (net (code "95") (name "unconnected-(IC10-PadNC)") (class "Default")
      (node (ref "IC10") (pin "NC") (pinfunction "NC_NC") (pintype "bidirectional"))
    )
    (net (code "96") (name "unconnected-(IC11-PadNC)") (class "Default")
      (node (ref "IC11") (pin "NC") (pinfunction "NC_NC") (pintype "bidirectional"))
    )
    (net (code "97") (name "unconnected-(IC12-1IN-Pad3)") (class "Default")
      (node (ref "IC12") (pin "3") (pinfunction "1IN_3") (pintype "bidirectional"))
    )
    (net (code "98") (name "unconnected-(IC12-1OUT-Pad2)") (class "Default")
      (node (ref "IC12") (pin "2") (pinfunction "1OUT_2") (pintype "bidirectional"))
    )
    (net (code "99") (name "unconnected-(IC12-6IN-Pad14)") (class "Default")
      (node (ref "IC12") (pin "14") (pinfunction "6IN_14") (pintype "bidirectional"))
    )
    (net (code "100") (name "unconnected-(IC12-6OUT-Pad15)") (class "Default")
      (node (ref "IC12") (pin "15") (pinfunction "6OUT_15") (pintype "bidirectional"))
    )
    (net (code "101") (name "unconnected-(IC12-NC-Pad16)") (class "Default")
      (node (ref "IC12") (pin "16") (pinfunction "NC_16") (pintype "bidirectional"))
    )
    (net (code "102") (name "unconnected-(IC12-NC2-Pad13)") (class "Default")
      (node (ref "IC12") (pin "13") (pinfunction "NC2_13") (pintype "bidirectional"))
    )
    (net (code "103") (name "unconnected-(PORT1-Pad2)") (class "Default")
      (node (ref "PORT1") (pin "2") (pinfunction "2_2") (pintype "bidirectional"))
    )
    (net (code "104") (name "unconnected-(PORT1-Pad8)") (class "Default")
      (node (ref "PORT1") (pin "8") (pinfunction "8_8") (pintype "bidirectional"))
    )
    (net (code "105") (name "unconnected-(PORT2-Pad2)") (class "Default")
      (node (ref "PORT2") (pin "2") (pinfunction "2_2") (pintype "bidirectional"))
    )
    (net (code "106") (name "unconnected-(PORT2-Pad8)") (class "Default")
      (node (ref "PORT2") (pin "8") (pinfunction "8_8") (pintype "bidirectional"))
    )
    (net (code "107") (name "unconnected-(PORT3-Pad2)") (class "Default")
      (node (ref "PORT3") (pin "2") (pinfunction "2_2") (pintype "bidirectional"))
    )
    (net (code "108") (name "unconnected-(PORT3-Pad8)") (class "Default")
      (node (ref "PORT3") (pin "8") (pinfunction "8_8") (pintype "bidirectional"))
    )
    (net (code "109") (name "unconnected-(PORT4-Pad2)") (class "Default")
      (node (ref "PORT4") (pin "2") (pinfunction "2_2") (pintype "bidirectional"))
    )
    (net (code "110") (name "unconnected-(PORT4-Pad8)") (class "Default")
      (node (ref "PORT4") (pin "8") (pinfunction "8_8") (pintype "bidirectional"))
    )
    (net (code "111") (name "unconnected-(SERIAL1-Pad5)") (class "Default")
      (node (ref "SERIAL1") (pin "5") (pinfunction "5_5") (pintype "bidirectional"))
    )
    (net (code "112") (name "unconnected-(SERIAL1-Pad6)") (class "Default")
      (node (ref "SERIAL1") (pin "6") (pinfunction "6_6") (pintype "bidirectional"))
    )
    (net (code "113") (name "unconnected-(SERIAL1-Pad7)") (class "Default")
      (node (ref "SERIAL1") (pin "7") (pinfunction "7_7") (pintype "bidirectional"))
    )
    (net (code "114") (name "unconnected-(SERIAL1-Pad8)") (class "Default")
      (node (ref "SERIAL1") (pin "8") (pinfunction "8_8") (pintype "bidirectional"))
    )
    (net (code "115") (name "unconnected-(SERIAL2-Pad5)") (class "Default")
      (node (ref "SERIAL2") (pin "5") (pinfunction "5_5") (pintype "bidirectional"))
    )
    (net (code "116") (name "unconnected-(SERIAL2-Pad6)") (class "Default")
      (node (ref "SERIAL2") (pin "6") (pinfunction "6_6") (pintype "bidirectional"))
    )
    (net (code "117") (name "unconnected-(SERIAL2-Pad7)") (class "Default")
      (node (ref "SERIAL2") (pin "7") (pinfunction "7_7") (pintype "bidirectional"))
    )
    (net (code "118") (name "unconnected-(SERIAL2-Pad8)") (class "Default")
      (node (ref "SERIAL2") (pin "8") (pinfunction "8_8") (pintype "bidirectional"))
    )
    (net (code "119") (name "unconnected-(SERIAL3-Pad7)") (class "Default")
      (node (ref "SERIAL3") (pin "7") (pinfunction "7_7") (pintype "bidirectional"))
    )
    (net (code "120") (name "unconnected-(SERIAL3-Pad8)") (class "Default")
      (node (ref "SERIAL3") (pin "8") (pinfunction "8_8") (pintype "bidirectional"))
    )
    (net (code "121") (name "unconnected-(SERIAL4-Pad7)") (class "Default")
      (node (ref "SERIAL4") (pin "7") (pinfunction "7_7") (pintype "bidirectional"))
    )
    (net (code "122") (name "unconnected-(SERIAL4-Pad8)") (class "Default")
      (node (ref "SERIAL4") (pin "8") (pinfunction "8_8") (pintype "bidirectional"))
    )
    (net (code "123") (name "unconnected-(SERIAL5-Pad7)") (class "Default")
      (node (ref "SERIAL5") (pin "7") (pinfunction "7_7") (pintype "bidirectional"))
    )
    (net (code "124") (name "unconnected-(SERIAL5-Pad8)") (class "Default")
      (node (ref "SERIAL5") (pin "8") (pinfunction "8_8") (pintype "bidirectional"))
    )
    (net (code "125") (name "unconnected-(U$1-11{slash}MOSI0-Pad11)") (class "Default")
      (node (ref "U$1") (pin "11") (pinfunction "11/MOSI0_11") (pintype "bidirectional"))
    )
    (net (code "126") (name "unconnected-(U$1-12{slash}MISO0-Pad12)") (class "Default")
      (node (ref "U$1") (pin "12") (pinfunction "12/MISO0_12") (pintype "bidirectional"))
    )
    (net (code "127") (name "unconnected-(U$1-13{slash}SCK0{slash}LED-Pad13)") (class "Default")
      (node (ref "U$1") (pin "13") (pinfunction "13/SCK0/LED_13") (pintype "bidirectional"))
    )
    (net (code "128") (name "unconnected-(U$1-29{slash}T{slash}PWM-Pad29)") (class "Default")
      (node (ref "U$1") (pin "29") (pinfunction "29/T/PWM_29") (pintype "bidirectional"))
    )
    (net (code "129") (name "unconnected-(U$1-30{slash}T{slash}PWM-Pad30)") (class "Default")
      (node (ref "U$1") (pin "30") (pinfunction "30/T/PWM_30") (pintype "bidirectional"))
    )
    (net (code "130") (name "unconnected-(U$1-A21{slash}DAC0-PadA21)") (class "Default")
      (node (ref "U$1") (pin "A21") (pinfunction "A21/DAC0_A21") (pintype "bidirectional"))
    )
    (net (code "131") (name "unconnected-(U$1-A22{slash}DAC1-PadA22)") (class "Default")
      (node (ref "U$1") (pin "A22") (pinfunction "A22/DAC1_A22") (pintype "bidirectional"))
    )
    (net (code "132") (name "unconnected-(U$1-Pad24)") (class "Default")
      (node (ref "U$1") (pin "24") (pinfunction "24_24") (pintype "bidirectional"))
    )
    (net (code "133") (name "unconnected-(U$1-Pad25)") (class "Default")
      (node (ref "U$1") (pin "25") (pinfunction "25_25") (pintype "bidirectional"))
    )
    (net (code "134") (name "unconnected-(U$1-Pad26)") (class "Default")
      (node (ref "U$1") (pin "26") (pinfunction "26_26") (pintype "bidirectional"))
    )
    (net (code "135") (name "unconnected-(U$1-Pad27)") (class "Default")
      (node (ref "U$1") (pin "27") (pinfunction "27_27") (pintype "bidirectional"))
    )
    (net (code "136") (name "unconnected-(U$1-Pad28)") (class "Default")
      (node (ref "U$1") (pin "28") (pinfunction "28_28") (pintype "bidirectional"))
    )
  )
)
